# Base_Station_1_8.net
KiCad netlist of a schematic drawn in EAGLE
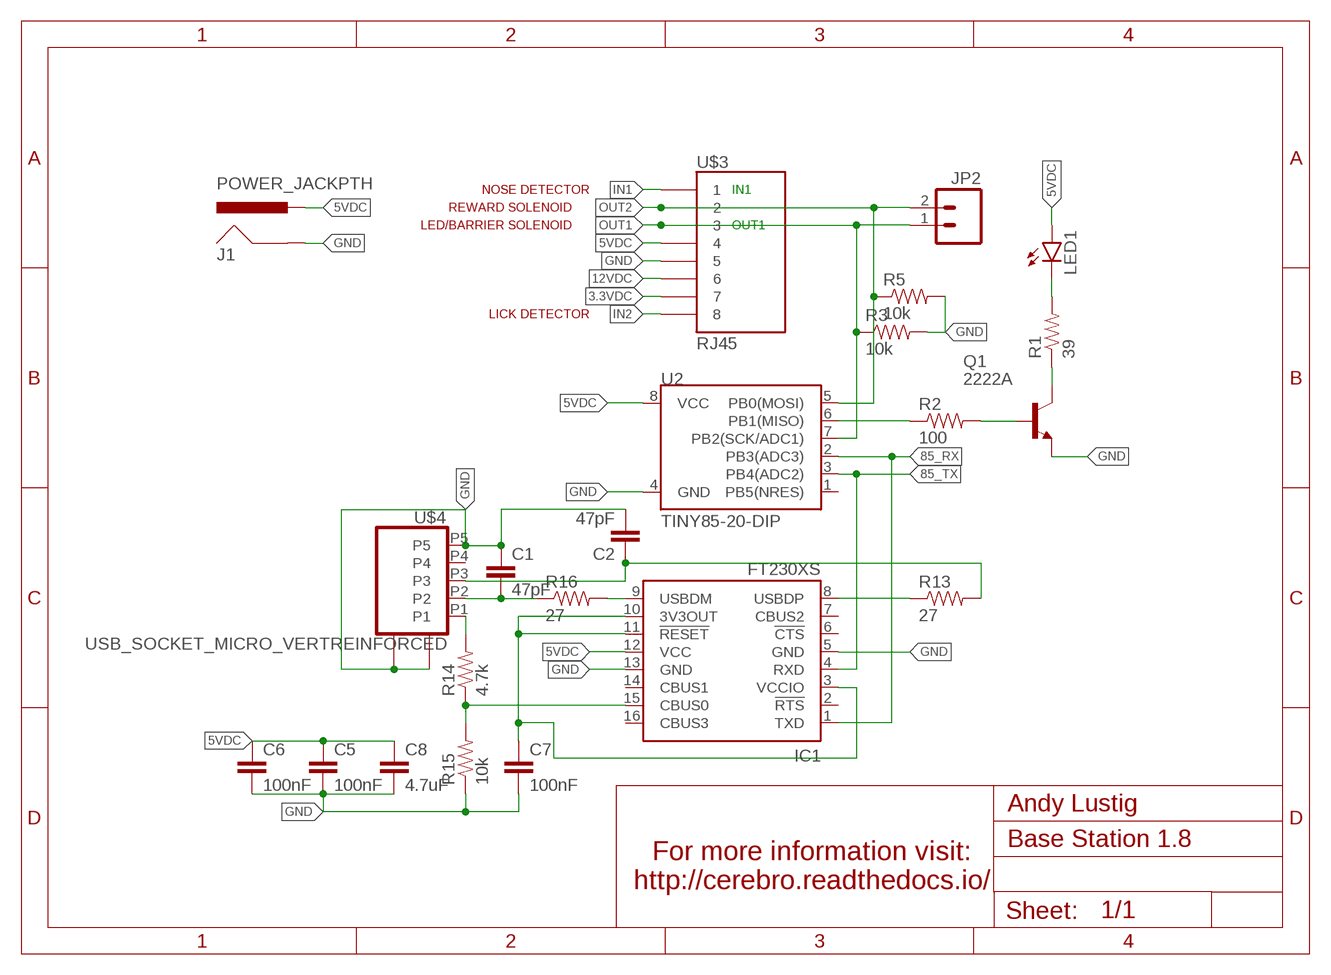
[diagram p0: schematic, sheet 1]

(export (version "E")
  (design (tool "Eeschema 10.0.6"))
  (components
    (comp (ref "C1")
      (value "47pF")
      (footprint "eagle-import:CAP-PTH-SMALL")
      (libsource (lib "eagle-import") (part "CAPPTH"))
    )
    (comp (ref "C2")
      (value "47pF")
      (footprint "eagle-import:CAP-PTH-SMALL")
      (libsource (lib "eagle-import") (part "CAPPTH"))
    )
    (comp (ref "C5")
      (value "100nF")
      (footprint "eagle-import:CAP-PTH-SMALL")
      (libsource (lib "eagle-import") (part "CAPPTH"))
    )
    (comp (ref "C6")
      (value "100nF")
      (footprint "eagle-import:CAP-PTH-SMALL")
      (libsource (lib "eagle-import") (part "CAPPTH"))
    )
    (comp (ref "C7")
      (value "100nF")
      (footprint "eagle-import:CAP-PTH-SMALL")
      (libsource (lib "eagle-import") (part "CAPPTH"))
    )
    (comp (ref "C8")
      (value "4.7uF")
      (footprint "eagle-import:CAP-PTH-SMALL")
      (libsource (lib "eagle-import") (part "CAPPTH"))
    )
    (comp (ref "IC1")
      (value "FT230XS")
      (footprint "eagle-import:SSOP16")
      (libsource (lib "eagle-import") (part "FT230XS"))
    )
    (comp (ref "J1")
      (value "POWER_JACKPTH")
      (footprint "eagle-import:POWER_JACK_PTH")
      (libsource (lib "eagle-import") (part "POWER_JACKPTH"))
    )
    (comp (ref "JP2")
      (value "M021X02_NO_SILK")
      (footprint "eagle-import:1X02_NO_SILK")
      (libsource (lib "eagle-import") (part "M021X02_NO_SILK"))
    )
    (comp (ref "LED1")
      (value "LED")
      (footprint "eagle-import:PLCC-2")
      (libsource (lib "eagle-import") (part "LED"))
    )
    (comp (ref "Q1")
      (value "2222A")
      (footprint "eagle-import:TO92-EBC-OVAL")
      (libsource (lib "eagle-import") (part "2N2222"))
    )
    (comp (ref "R1")
      (value "39")
      (footprint "eagle-import:AXIAL-0.1")
      (libsource (lib "eagle-import") (part "RESISTORPTH-1/4W-VERT"))
    )
    (comp (ref "R2")
      (value "100")
      (footprint "eagle-import:AXIAL-0.1")
      (libsource (lib "eagle-import") (part "RESISTORPTH-1/4W-VERT"))
    )
    (comp (ref "R3")
      (value "10k")
      (footprint "eagle-import:AXIAL-0.1")
      (libsource (lib "eagle-import") (part "RESISTORPTH-1/4W-VERT"))
    )
    (comp (ref "R5")
      (value "10k")
      (footprint "eagle-import:AXIAL-0.1")
      (libsource (lib "eagle-import") (part "RESISTORPTH-1/4W-VERT"))
    )
    (comp (ref "R13")
      (value "27")
      (footprint "eagle-import:AXIAL-0.1")
      (libsource (lib "eagle-import") (part "RESISTORPTH-1/4W-VERT"))
    )
    (comp (ref "R14")
      (value "4.7k")
      (footprint "eagle-import:AXIAL-0.1")
      (libsource (lib "eagle-import") (part "RESISTORPTH-1/4W-VERT"))
    )
    (comp (ref "R15")
      (value "10k")
      (footprint "eagle-import:AXIAL-0.1")
      (libsource (lib "eagle-import") (part "RESISTORPTH-1/4W-VERT"))
    )
    (comp (ref "R16")
      (value "27")
      (footprint "eagle-import:AXIAL-0.1")
      (libsource (lib "eagle-import") (part "RESISTORPTH-1/4W-VERT"))
    )
    (comp (ref "U$3")
      (value "RJ45")
      (footprint "eagle-import:RJ45-8")
      (libsource (lib "eagle-import") (part "RJ45"))
    )
    (comp (ref "U$4")
      (value "USB_SOCKET_MICRO_VERTREINFORCED")
      (footprint "eagle-import:USB_HORZ_REINFORCED_MICRO")
      (libsource (lib "eagle-import") (part "USB_SOCKET_MICRO_VERTREINFORCED"))
    )
    (comp (ref "U2")
      (value "TINY85-20-DIP")
      (footprint "eagle-import:DIP08")
      (libsource (lib "eagle-import") (part "ATTINY45TINY85-20-DIP"))
    )
  )
  (nets
    (net (code "1") (name "3.3VDC") (class "Default")
      (node (ref "U$3") (pin "7") (pinfunction "7_7") (pintype "bidirectional"))
    )
    (net (code "2") (name "5VDC") (class "Default")
      (node (ref "C5") (pin "1") (pinfunction "1_1") (pintype "passive"))
      (node (ref "C6") (pin "1") (pinfunction "1_1") (pintype "passive"))
      (node (ref "C8") (pin "1") (pinfunction "1_1") (pintype "passive"))
      (node (ref "IC1") (pin "12") (pinfunction "VCC_12") (pintype "power_in"))
      (node (ref "J1") (pin "PWR") (pinfunction "PWR_PWR") (pintype "bidirectional"))
      (node (ref "LED1") (pin "ANODE") (pinfunction "A_ANODE") (pintype "passive"))
      (node (ref "U$3") (pin "4") (pinfunction "4_4") (pintype "bidirectional"))
      (node (ref "U2") (pin "8") (pinfunction "VCC_8") (pintype "bidirectional"))
    )
    (net (code "3") (name "12VDC") (class "Default")
      (node (ref "U$3") (pin "6") (pinfunction "6_6") (pintype "bidirectional"))
    )
    (net (code "4") (name "85_RX") (class "Default")
      (node (ref "IC1") (pin "1") (pinfunction "TXD_1") (pintype "output"))
      (node (ref "U2") (pin "2") (pinfunction "PB3(ADC3)_2") (pintype "bidirectional"))
    )
    (net (code "5") (name "85_TX") (class "Default")
      (node (ref "IC1") (pin "4") (pinfunction "RXD_4") (pintype "input"))
      (node (ref "U2") (pin "3") (pinfunction "PB4(ADC2)_3") (pintype "bidirectional"))
    )
    (net (code "6") (name "GND") (class "Default")
      (node (ref "C1") (pin "1") (pinfunction "1_1") (pintype "passive"))
      (node (ref "C2") (pin "2") (pinfunction "2_2") (pintype "passive"))
      (node (ref "C5") (pin "2") (pinfunction "2_2") (pintype "passive"))
      (node (ref "C6") (pin "2") (pinfunction "2_2") (pintype "passive"))
      (node (ref "C7") (pin "2") (pinfunction "2_2") (pintype "passive"))
      (node (ref "C8") (pin "2") (pinfunction "2_2") (pintype "passive"))
      (node (ref "IC1") (pin "13") (pinfunction "GND_13") (pintype "power_in"))
      (node (ref "IC1") (pin "5") (pinfunction "GND_5") (pintype "power_in"))
      (node (ref "J1") (pin "GND") (pinfunction "GND_GND") (pintype "bidirectional"))
      (node (ref "Q1") (pin "E") (pinfunction "E_E") (pintype "passive"))
      (node (ref "R15") (pin "P$1") (pinfunction "1_P$1") (pintype "passive"))
      (node (ref "R3") (pin "P$2") (pinfunction "2_P$2") (pintype "passive"))
      (node (ref "R5") (pin "P$2") (pinfunction "2_P$2") (pintype "passive"))
      (node (ref "U$3") (pin "5") (pinfunction "5_5") (pintype "bidirectional"))
      (node (ref "U$4") (pin "G1") (pinfunction "P$1_G1") (pintype "bidirectional"))
      (node (ref "U$4") (pin "G2") (pinfunction "P$1_G2") (pintype "bidirectional"))
      (node (ref "U$4") (pin "P$1") (pinfunction "P$2_P$1") (pintype "bidirectional"))
      (node (ref "U$4") (pin "P$2") (pinfunction "P$2_P$2") (pintype "bidirectional"))
      (node (ref "U$4") (pin "P5") (pinfunction "P5_P5") (pintype "bidirectional"))
      (node (ref "U2") (pin "4") (pinfunction "GND_4") (pintype "bidirectional"))
    )
    (net (code "7") (name "IN1") (class "Default")
      (node (ref "U$3") (pin "1") (pinfunction "1_1") (pintype "bidirectional"))
    )
    (net (code "8") (name "IN2") (class "Default")
      (node (ref "U$3") (pin "8") (pinfunction "8_8") (pintype "bidirectional"))
    )
    (net (code "9") (name "Net-(IC1-3V3OUT)") (class "Default")
      (node (ref "C7") (pin "1") (pinfunction "1_1") (pintype "passive"))
      (node (ref "IC1") (pin "10") (pinfunction "3V3OUT_10") (pintype "output"))
      (node (ref "IC1") (pin "11") (pinfunction "~{RESET}_11") (pintype "input"))
      (node (ref "IC1") (pin "3") (pinfunction "VCCIO_3") (pintype "power_in"))
    )
    (net (code "10") (name "Net-(IC1-CBUS0)") (class "Default")
      (node (ref "IC1") (pin "15") (pinfunction "CBUS0_15") (pintype "bidirectional"))
      (node (ref "R14") (pin "P$1") (pinfunction "1_P$1") (pintype "passive"))
      (node (ref "R15") (pin "P$2") (pinfunction "2_P$2") (pintype "passive"))
    )
    (net (code "11") (name "Net-(IC1-USBDM)") (class "Default")
      (node (ref "IC1") (pin "9") (pinfunction "USBDM_9") (pintype "input"))
      (node (ref "R16") (pin "P$2") (pinfunction "2_P$2") (pintype "passive"))
    )
    (net (code "12") (name "Net-(IC1-USBDP)") (class "Default")
      (node (ref "IC1") (pin "8") (pinfunction "USBDP_8") (pintype "input"))
      (node (ref "R13") (pin "P$1") (pinfunction "1_P$1") (pintype "passive"))
    )
    (net (code "13") (name "Net-(LED1-C)") (class "Default")
      (node (ref "LED1") (pin "CATHODE") (pinfunction "C_CATHODE") (pintype "passive"))
      (node (ref "R1") (pin "P$2") (pinfunction "2_P$2") (pintype "passive"))
    )
    (net (code "14") (name "Net-(R1-1)") (class "Default")
      (node (ref "Q1") (pin "C") (pinfunction "C_C") (pintype "passive"))
      (node (ref "R1") (pin "P$1") (pinfunction "1_P$1") (pintype "passive"))
    )
    (net (code "15") (name "Net-(R2-1)") (class "Default")
      (node (ref "R2") (pin "P$1") (pinfunction "1_P$1") (pintype "passive"))
      (node (ref "U2") (pin "6") (pinfunction "PB1(MISO)_6") (pintype "bidirectional"))
    )
    (net (code "16") (name "Net-(R2-2)") (class "Default")
      (node (ref "Q1") (pin "B") (pinfunction "B_B") (pintype "passive"))
      (node (ref "R2") (pin "P$2") (pinfunction "2_P$2") (pintype "passive"))
    )
    (net (code "17") (name "Net-(R13-2)") (class "Default")
      (node (ref "C2") (pin "1") (pinfunction "1_1") (pintype "passive"))
      (node (ref "R13") (pin "P$2") (pinfunction "2_P$2") (pintype "passive"))
      (node (ref "U$4") (pin "P3") (pinfunction "P3_P3") (pintype "bidirectional"))
    )
    (net (code "18") (name "Net-(R14-2)") (class "Default")
      (node (ref "R14") (pin "P$2") (pinfunction "2_P$2") (pintype "passive"))
      (node (ref "U$4") (pin "P1") (pinfunction "P1_P1") (pintype "bidirectional"))
    )
    (net (code "19") (name "Net-(R16-1)") (class "Default")
      (node (ref "C1") (pin "2") (pinfunction "2_2") (pintype "passive"))
      (node (ref "R16") (pin "P$1") (pinfunction "1_P$1") (pintype "passive"))
      (node (ref "U$4") (pin "P2") (pinfunction "P2_P2") (pintype "bidirectional"))
    )
    (net (code "20") (name "OUT1") (class "Default")
      (node (ref "JP2") (pin "1") (pinfunction "1_1") (pintype "passive"))
      (node (ref "R3") (pin "P$1") (pinfunction "1_P$1") (pintype "passive"))
      (node (ref "U$3") (pin "3") (pinfunction "3_3") (pintype "bidirectional"))
      (node (ref "U2") (pin "7") (pinfunction "PB2(SCK/ADC1)_7") (pintype "bidirectional"))
    )
    (net (code "21") (name "OUT2") (class "Default")
      (node (ref "JP2") (pin "2") (pinfunction "2_2") (pintype "passive"))
      (node (ref "R5") (pin "P$1") (pinfunction "1_P$1") (pintype "passive"))
      (node (ref "U$3") (pin "2") (pinfunction "2_2") (pintype "bidirectional"))
      (node (ref "U2") (pin "5") (pinfunction "PB0(MOSI)_5") (pintype "bidirectional"))
    )
    (net (code "22") (name "unconnected-(IC1-CBUS1-Pad14)") (class "Default")
      (node (ref "IC1") (pin "14") (pinfunction "CBUS1_14") (pintype "bidirectional"))
    )
    (net (code "23") (name "unconnected-(IC1-CBUS2-Pad7)") (class "Default")
      (node (ref "IC1") (pin "7") (pinfunction "CBUS2_7") (pintype "bidirectional"))
    )
    (net (code "24") (name "unconnected-(IC1-CBUS3-Pad16)") (class "Default")
      (node (ref "IC1") (pin "16") (pinfunction "CBUS3_16") (pintype "bidirectional"))
    )
    (net (code "25") (name "unconnected-(IC1-~{CTS}-Pad6)") (class "Default")
      (node (ref "IC1") (pin "6") (pinfunction "~{CTS}_6") (pintype "input"))
    )
    (net (code "26") (name "unconnected-(IC1-~{RTS}-Pad2)") (class "Default")
      (node (ref "IC1") (pin "2") (pinfunction "~{RTS}_2") (pintype "output"))
    )
    (net (code "27") (name "unconnected-(U$4-PadP4)") (class "Default")
      (node (ref "U$4") (pin "P4") (pinfunction "P4_P4") (pintype "bidirectional"))
    )
    (net (code "28") (name "unconnected-(U2-PB5(NRES)-Pad1)") (class "Default")
      (node (ref "U2") (pin "1") (pinfunction "PB5(NRES)_1") (pintype "bidirectional"))
    )
  )
)
